# test_brd_add_gnd.net
KiCad netlist of a schematic drawn in EAGLE
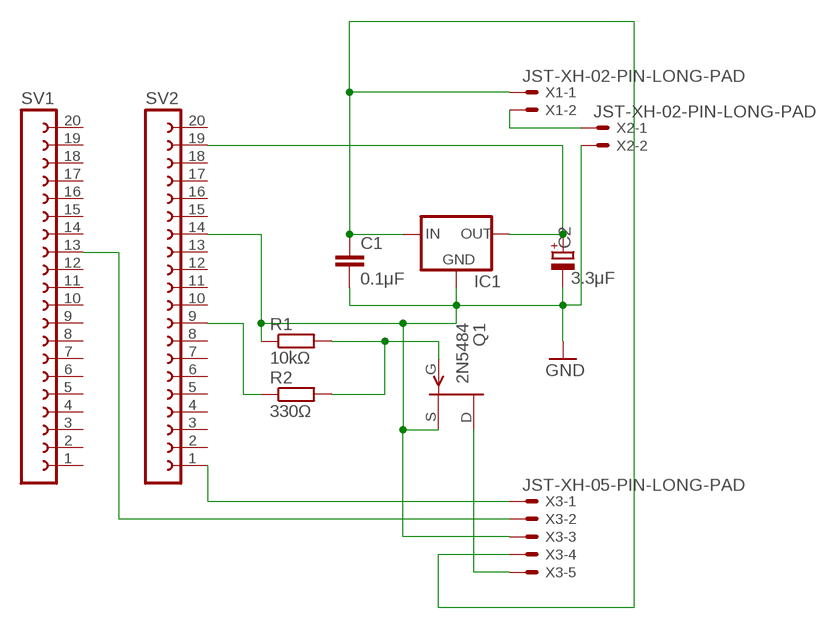
[diagram p0: schematic, sheet 1]

(export (version "E")
  (design (tool "Eeschema 10.0.6"))
  (components
    (comp (ref "C1")
      (value "0.1μF")
      (footprint "eagle-import:C025-040X050")
      (libsource (lib "eagle-import") (part "C-EU025-040X050"))
    )
    (comp (ref "C2")
      (value "3.3μF")
      (footprint "eagle-import:E2,5-5")
      (libsource (lib "eagle-import") (part "CPOL-EUE2.5-5"))
    )
    (comp (ref "IC1")
      (value "78XXS")
      (footprint "eagle-import:78XXS")
      (libsource (lib "eagle-import") (part "78XXS"))
    )
    (comp (ref "Q1")
      (value "2N5484")
      (footprint "eagle-import:TO92-")
      (libsource (lib "eagle-import") (part "?5482N4"))
    )
    (comp (ref "R1")
      (value "10kΩ")
      (footprint "eagle-import:0207_10")
      (libsource (lib "eagle-import") (part "R-EU_0207/10"))
    )
    (comp (ref "R2")
      (value "330Ω")
      (footprint "eagle-import:0207_10")
      (libsource (lib "eagle-import") (part "R-EU_0207/10"))
    )
    (comp (ref "SV1")
      (value "FE20-1")
      (footprint "eagle-import:FE20")
      (libsource (lib "eagle-import") (part "FE20-1"))
    )
    (comp (ref "SV2")
      (value "FE20-1")
      (footprint "eagle-import:FE20")
      (libsource (lib "eagle-import") (part "FE20-1"))
    )
    (comp (ref "X1")
      (value "JST-XH-02-PIN-LONG-PAD")
      (footprint "eagle-import:JST-XH-02-PACKAGE-LONG-PAD")
      (libsource (lib "eagle-import") (part "JST-XH-02-PIN-LONG-PAD"))
    )
    (comp (ref "X2")
      (value "JST-XH-02-PIN-LONG-PAD")
      (footprint "eagle-import:JST-XH-02-PACKAGE-LONG-PAD")
      (libsource (lib "eagle-import") (part "JST-XH-02-PIN-LONG-PAD"))
    )
    (comp (ref "X3")
      (value "JST-XH-05-PIN-LONG-PAD")
      (footprint "eagle-import:JST-XH-05-PACKAGE-LONG-PAD")
      (libsource (lib "eagle-import") (part "JST-XH-05-PIN-LONG-PAD"))
    )
  )
  (nets
    (net (code "1") (name "GND") (class "Default")
      (node (ref "C1") (pin "2") (pinfunction "2_2") (pintype "passive"))
      (node (ref "C2") (pin "-") (pinfunction "-_-") (pintype "passive"))
      (node (ref "IC1") (pin "GND") (pinfunction "GND_GND") (pintype "input"))
      (node (ref "Q1") (pin "2") (pinfunction "S_2") (pintype "passive"))
      (node (ref "R1") (pin "1") (pinfunction "1_1") (pintype "passive"))
      (node (ref "SV2") (pin "14") (pinfunction "14_14") (pintype "passive"))
      (node (ref "X2") (pin "2") (pinfunction "S_2") (pintype "passive"))
      (node (ref "X3") (pin "3") (pinfunction "S_3") (pintype "passive"))
    )
    (net (code "2") (name "Net-(C2-Pad+)") (class "Default")
      (node (ref "C2") (pin "+") (pinfunction "+_+") (pintype "passive"))
      (node (ref "IC1") (pin "OUT") (pinfunction "OUT_OUT") (pintype "passive"))
      (node (ref "SV2") (pin "19") (pinfunction "19_19") (pintype "passive"))
    )
    (net (code "3") (name "Net-(Q1-D)") (class "Default")
      (node (ref "Q1") (pin "3") (pinfunction "D_3") (pintype "passive"))
      (node (ref "X3") (pin "5") (pinfunction "S_5") (pintype "passive"))
    )
    (net (code "4") (name "Net-(Q1-G)") (class "Default")
      (node (ref "Q1") (pin "1") (pinfunction "G_1") (pintype "passive"))
      (node (ref "R1") (pin "2") (pinfunction "2_2") (pintype "passive"))
      (node (ref "R2") (pin "2") (pinfunction "2_2") (pintype "passive"))
    )
    (net (code "5") (name "Net-(R2-Pad1)") (class "Default")
      (node (ref "R2") (pin "1") (pinfunction "1_1") (pintype "passive"))
      (node (ref "SV2") (pin "9") (pinfunction "9_9") (pintype "passive"))
    )
    (net (code "6") (name "Net-(X1A-S)") (class "Default")
      (node (ref "C1") (pin "1") (pinfunction "1_1") (pintype "passive"))
      (node (ref "IC1") (pin "IN") (pinfunction "IN_IN") (pintype "input"))
      (node (ref "X1") (pin "1") (pinfunction "S_1") (pintype "passive"))
      (node (ref "X3") (pin "4") (pinfunction "S_4") (pintype "passive"))
    )
    (net (code "7") (name "Net-(X1B-S)") (class "Default")
      (node (ref "X1") (pin "2") (pinfunction "S_2") (pintype "passive"))
      (node (ref "X2") (pin "1") (pinfunction "S_1") (pintype "passive"))
    )
    (net (code "8") (name "Net-(X3A-S)") (class "Default")
      (node (ref "SV2") (pin "1") (pinfunction "1_1") (pintype "passive"))
      (node (ref "X3") (pin "1") (pinfunction "S_1") (pintype "passive"))
    )
    (net (code "9") (name "Net-(X3B-S)") (class "Default")
      (node (ref "SV1") (pin "13") (pinfunction "13_13") (pintype "passive"))
      (node (ref "X3") (pin "2") (pinfunction "S_2") (pintype "passive"))
    )
    (net (code "10") (name "unconnected-(SV1-Pad1)") (class "Default")
      (node (ref "SV1") (pin "1") (pinfunction "1_1") (pintype "passive"))
    )
    (net (code "11") (name "unconnected-(SV1-Pad2)") (class "Default")
      (node (ref "SV1") (pin "2") (pinfunction "2_2") (pintype "passive"))
    )
    (net (code "12") (name "unconnected-(SV1-Pad3)") (class "Default")
      (node (ref "SV1") (pin "3") (pinfunction "3_3") (pintype "passive"))
    )
    (net (code "13") (name "unconnected-(SV1-Pad4)") (class "Default")
      (node (ref "SV1") (pin "4") (pinfunction "4_4") (pintype "passive"))
    )
    (net (code "14") (name "unconnected-(SV1-Pad5)") (class "Default")
      (node (ref "SV1") (pin "5") (pinfunction "5_5") (pintype "passive"))
    )
    (net (code "15") (name "unconnected-(SV1-Pad6)") (class "Default")
      (node (ref "SV1") (pin "6") (pinfunction "6_6") (pintype "passive"))
    )
    (net (code "16") (name "unconnected-(SV1-Pad7)") (class "Default")
      (node (ref "SV1") (pin "7") (pinfunction "7_7") (pintype "passive"))
    )
    (net (code "17") (name "unconnected-(SV1-Pad8)") (class "Default")
      (node (ref "SV1") (pin "8") (pinfunction "8_8") (pintype "passive"))
    )
    (net (code "18") (name "unconnected-(SV1-Pad9)") (class "Default")
      (node (ref "SV1") (pin "9") (pinfunction "9_9") (pintype "passive"))
    )
    (net (code "19") (name "unconnected-(SV1-Pad10)") (class "Default")
      (node (ref "SV1") (pin "10") (pinfunction "10_10") (pintype "passive"))
    )
    (net (code "20") (name "unconnected-(SV1-Pad11)") (class "Default")
      (node (ref "SV1") (pin "11") (pinfunction "11_11") (pintype "passive"))
    )
    (net (code "21") (name "unconnected-(SV1-Pad12)") (class "Default")
      (node (ref "SV1") (pin "12") (pinfunction "12_12") (pintype "passive"))
    )
    (net (code "22") (name "unconnected-(SV1-Pad14)") (class "Default")
      (node (ref "SV1") (pin "14") (pinfunction "14_14") (pintype "passive"))
    )
    (net (code "23") (name "unconnected-(SV1-Pad15)") (class "Default")
      (node (ref "SV1") (pin "15") (pinfunction "15_15") (pintype "passive"))
    )
    (net (code "24") (name "unconnected-(SV1-Pad16)") (class "Default")
      (node (ref "SV1") (pin "16") (pinfunction "16_16") (pintype "passive"))
    )
    (net (code "25") (name "unconnected-(SV1-Pad17)") (class "Default")
      (node (ref "SV1") (pin "17") (pinfunction "17_17") (pintype "passive"))
    )
    (net (code "26") (name "unconnected-(SV1-Pad18)") (class "Default")
      (node (ref "SV1") (pin "18") (pinfunction "18_18") (pintype "passive"))
    )
    (net (code "27") (name "unconnected-(SV1-Pad19)") (class "Default")
      (node (ref "SV1") (pin "19") (pinfunction "19_19") (pintype "passive"))
    )
    (net (code "28") (name "unconnected-(SV1-Pad20)") (class "Default")
      (node (ref "SV1") (pin "20") (pinfunction "20_20") (pintype "passive"))
    )
    (net (code "29") (name "unconnected-(SV2-Pad2)") (class "Default")
      (node (ref "SV2") (pin "2") (pinfunction "2_2") (pintype "passive"))
    )
    (net (code "30") (name "unconnected-(SV2-Pad3)") (class "Default")
      (node (ref "SV2") (pin "3") (pinfunction "3_3") (pintype "passive"))
    )
    (net (code "31") (name "unconnected-(SV2-Pad4)") (class "Default")
      (node (ref "SV2") (pin "4") (pinfunction "4_4") (pintype "passive"))
    )
    (net (code "32") (name "unconnected-(SV2-Pad5)") (class "Default")
      (node (ref "SV2") (pin "5") (pinfunction "5_5") (pintype "passive"))
    )
    (net (code "33") (name "unconnected-(SV2-Pad6)") (class "Default")
      (node (ref "SV2") (pin "6") (pinfunction "6_6") (pintype "passive"))
    )
    (net (code "34") (name "unconnected-(SV2-Pad7)") (class "Default")
      (node (ref "SV2") (pin "7") (pinfunction "7_7") (pintype "passive"))
    )
    (net (code "35") (name "unconnected-(SV2-Pad8)") (class "Default")
      (node (ref "SV2") (pin "8") (pinfunction "8_8") (pintype "passive"))
    )
    (net (code "36") (name "unconnected-(SV2-Pad10)") (class "Default")
      (node (ref "SV2") (pin "10") (pinfunction "10_10") (pintype "passive"))
    )
    (net (code "37") (name "unconnected-(SV2-Pad11)") (class "Default")
      (node (ref "SV2") (pin "11") (pinfunction "11_11") (pintype "passive"))
    )
    (net (code "38") (name "unconnected-(SV2-Pad12)") (class "Default")
      (node (ref "SV2") (pin "12") (pinfunction "12_12") (pintype "passive"))
    )
    (net (code "39") (name "unconnected-(SV2-Pad13)") (class "Default")
      (node (ref "SV2") (pin "13") (pinfunction "13_13") (pintype "passive"))
    )
    (net (code "40") (name "unconnected-(SV2-Pad15)") (class "Default")
      (node (ref "SV2") (pin "15") (pinfunction "15_15") (pintype "passive"))
    )
    (net (code "41") (name "unconnected-(SV2-Pad16)") (class "Default")
      (node (ref "SV2") (pin "16") (pinfunction "16_16") (pintype "passive"))
    )
    (net (code "42") (name "unconnected-(SV2-Pad17)") (class "Default")
      (node (ref "SV2") (pin "17") (pinfunction "17_17") (pintype "passive"))
    )
    (net (code "43") (name "unconnected-(SV2-Pad18)") (class "Default")
      (node (ref "SV2") (pin "18") (pinfunction "18_18") (pintype "passive"))
    )
    (net (code "44") (name "unconnected-(SV2-Pad20)") (class "Default")
      (node (ref "SV2") (pin "20") (pinfunction "20_20") (pintype "passive"))
    )
  )
)
